# v11.net
KiCad netlist of a schematic drawn in EAGLE
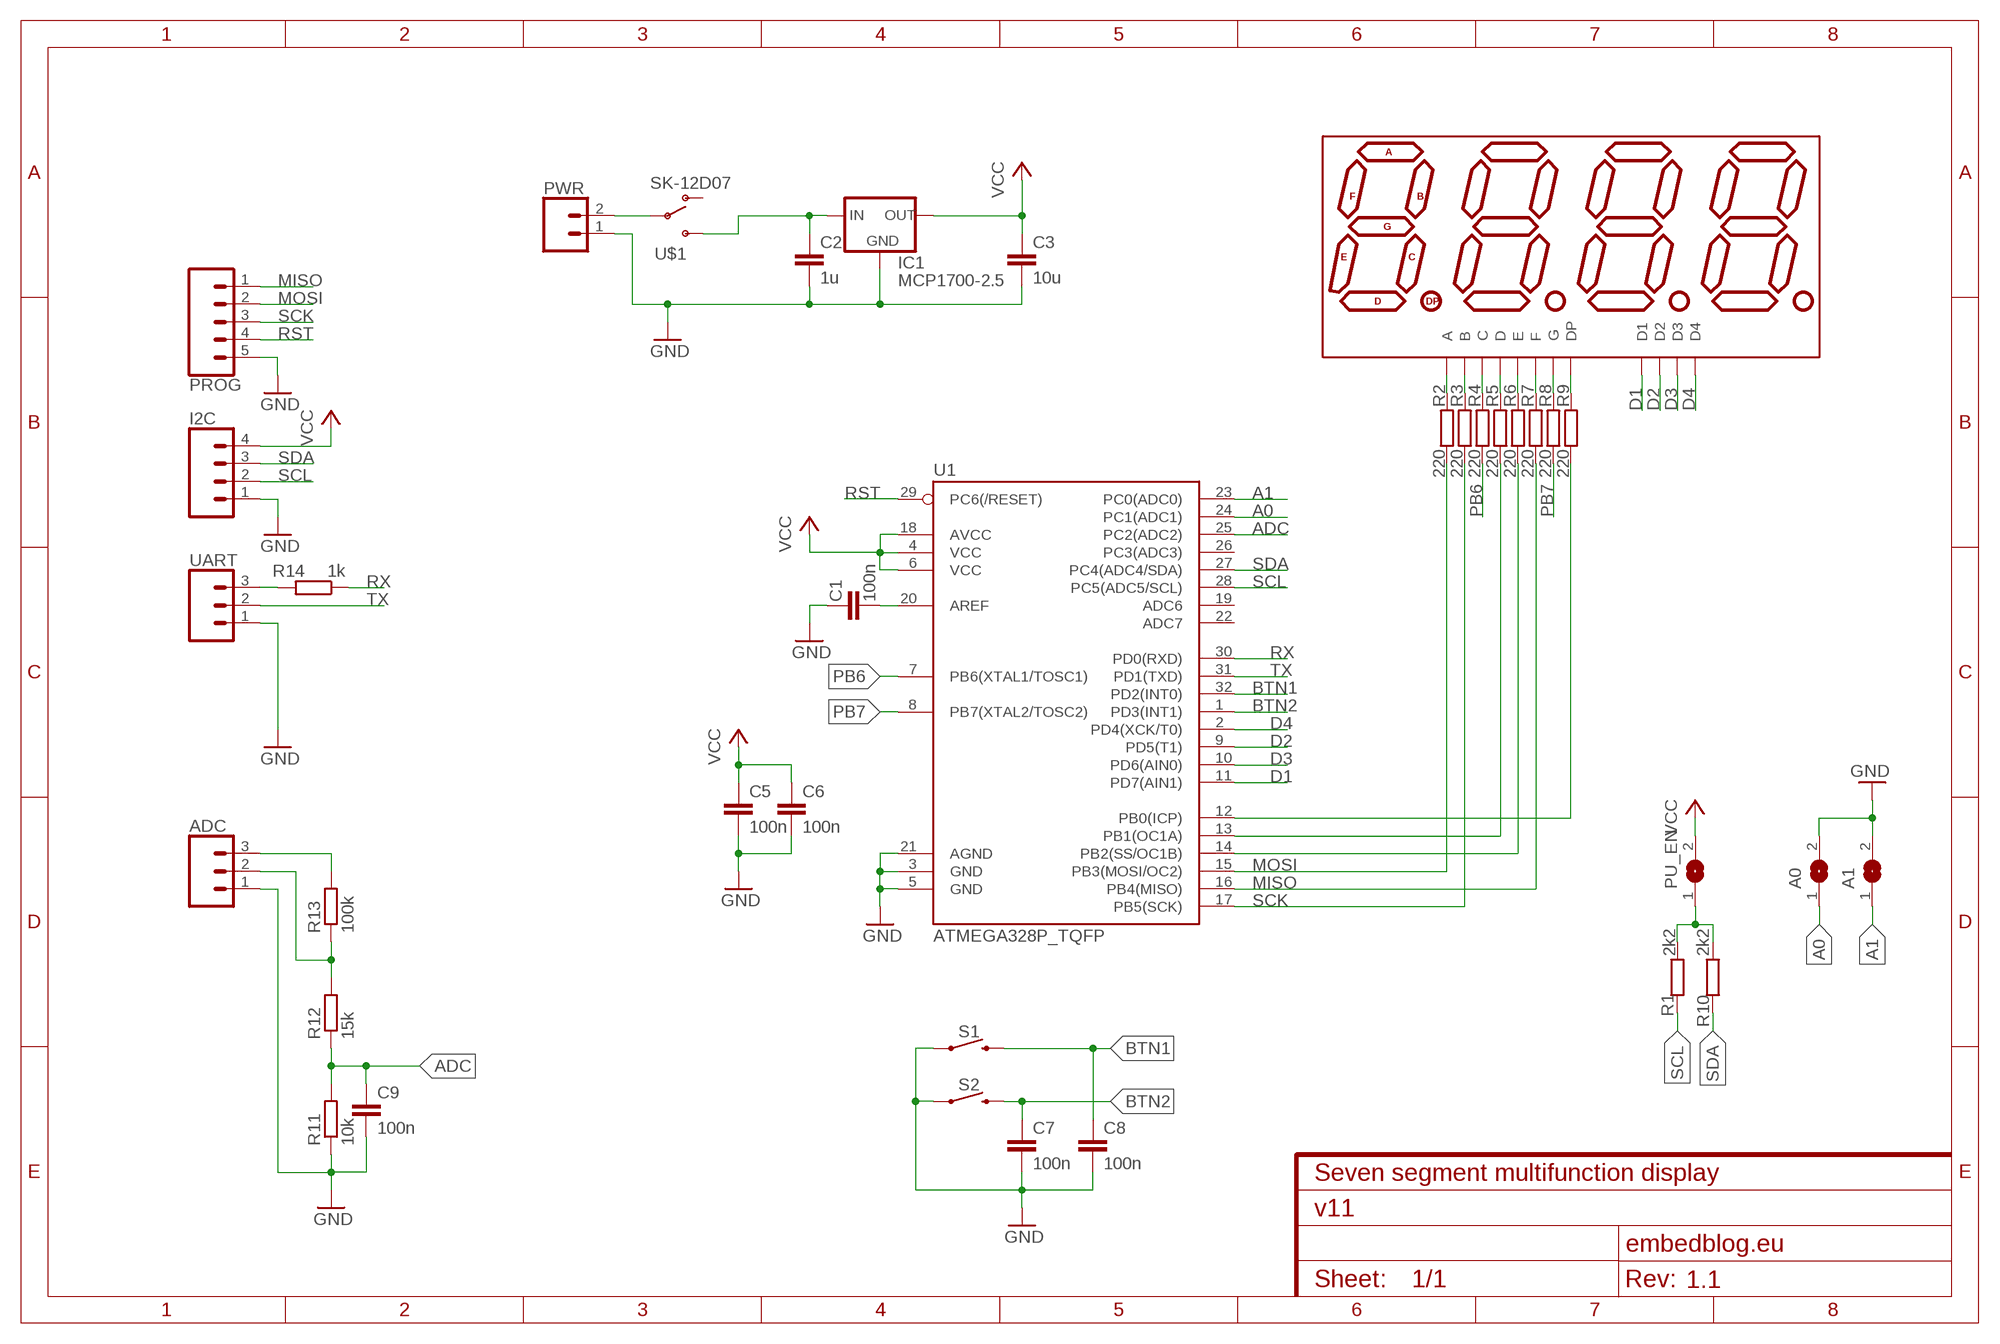
[diagram p0: schematic, sheet 1]

(export (version "E")
  (design (tool "Eeschema 10.0.6"))
  (components
    (comp (ref "A0") (value "SJ") (footprint "eagle-import:SJ") (libsource (lib "eagle-import") (part "SJ")))
    (comp (ref "A1") (value "SJ") (footprint "eagle-import:SJ") (libsource (lib "eagle-import") (part "SJ")))
    (comp (ref "ADC")
      (value "455-1750-1-ND")
      (footprint "eagle-import:1X03")
      (libsource (lib "eagle-import") (part "CONN_03"))
    )
    (comp (ref "C1")
      (value "100n")
      (footprint "eagle-import:C1206")
      (libsource (lib "eagle-import") (part "C-EUC1206"))
    )
    (comp (ref "C2")
      (value "1u")
      (footprint "eagle-import:C1206")
      (libsource (lib "eagle-import") (part "C-EUC1206"))
    )
    (comp (ref "C3")
      (value "10u")
      (footprint "eagle-import:C1206")
      (libsource (lib "eagle-import") (part "C-EUC1206"))
    )
    (comp (ref "C5")
      (value "100n")
      (footprint "eagle-import:C1206")
      (libsource (lib "eagle-import") (part "C-EUC1206"))
    )
    (comp (ref "C6")
      (value "100n")
      (footprint "eagle-import:C1206")
      (libsource (lib "eagle-import") (part "C-EUC1206"))
    )
    (comp (ref "C7")
      (value "100n")
      (footprint "eagle-import:C1206")
      (libsource (lib "eagle-import") (part "C-EUC1206"))
    )
    (comp (ref "C8")
      (value "100n")
      (footprint "eagle-import:C1206")
      (libsource (lib "eagle-import") (part "C-EUC1206"))
    )
    (comp (ref "C9")
      (value "100n")
      (footprint "eagle-import:C1206")
      (libsource (lib "eagle-import") (part "C-EUC1206"))
    )
    (comp (ref "D1")
      (value "7-SEG_0.56INCH")
      (footprint "eagle-import:7SEG_0.56INCH")
      (libsource (lib "eagle-import") (part "7-SEG_0.56INCH"))
    )
    (comp (ref "I2C")
      (value "CONN_04")
      (footprint "eagle-import:1X04")
      (libsource (lib "eagle-import") (part "CONN_04"))
    )
    (comp (ref "IC1")
      (value "MCP1700-2.5")
      (footprint "eagle-import:SOT23")
      (libsource (lib "eagle-import") (part "XC63FPM"))
    )
    (comp (ref "PROG")
      (value "CONN_05")
      (footprint "eagle-import:1X05")
      (libsource (lib "eagle-import") (part "CONN_05"))
    )
    (comp (ref "PU_EN")
      (value "SJ")
      (footprint "eagle-import:SJ")
      (libsource (lib "eagle-import") (part "SJ"))
    )
    (comp (ref "PWR")
      (value "CONN_02")
      (footprint "eagle-import:1X02")
      (libsource (lib "eagle-import") (part "CONN_02"))
    )
    (comp (ref "R1")
      (value "2k2")
      (footprint "eagle-import:R1206")
      (libsource (lib "eagle-import") (part "R-EU_R1206"))
    )
    (comp (ref "R2")
      (value "220")
      (footprint "eagle-import:R1206")
      (libsource (lib "eagle-import") (part "R-EU_R1206"))
    )
    (comp (ref "R3")
      (value "220")
      (footprint "eagle-import:R1206")
      (libsource (lib "eagle-import") (part "R-EU_R1206"))
    )
    (comp (ref "R4")
      (value "220")
      (footprint "eagle-import:R1206")
      (libsource (lib "eagle-import") (part "R-EU_R1206"))
    )
    (comp (ref "R5")
      (value "220")
      (footprint "eagle-import:R1206")
      (libsource (lib "eagle-import") (part "R-EU_R1206"))
    )
    (comp (ref "R6")
      (value "220")
      (footprint "eagle-import:R1206")
      (libsource (lib "eagle-import") (part "R-EU_R1206"))
    )
    (comp (ref "R7")
      (value "220")
      (footprint "eagle-import:R1206")
      (libsource (lib "eagle-import") (part "R-EU_R1206"))
    )
    (comp (ref "R8")
      (value "220")
      (footprint "eagle-import:R1206")
      (libsource (lib "eagle-import") (part "R-EU_R1206"))
    )
    (comp (ref "R9")
      (value "220")
      (footprint "eagle-import:R1206")
      (libsource (lib "eagle-import") (part "R-EU_R1206"))
    )
    (comp (ref "R10")
      (value "2k2")
      (footprint "eagle-import:R1206")
      (libsource (lib "eagle-import") (part "R-EU_R1206"))
    )
    (comp (ref "R11")
      (value "10k")
      (footprint "eagle-import:R1206")
      (libsource (lib "eagle-import") (part "R-EU_R1206"))
    )
    (comp (ref "R12")
      (value "15k")
      (footprint "eagle-import:R1206")
      (libsource (lib "eagle-import") (part "R-EU_R1206"))
    )
    (comp (ref "R13")
      (value "100k")
      (footprint "eagle-import:R1206")
      (libsource (lib "eagle-import") (part "R-EU_R1206"))
    )
    (comp (ref "R14")
      (value "1k")
      (footprint "eagle-import:R1206")
      (libsource (lib "eagle-import") (part "R-EU_R1206"))
    )
    (comp (ref "S1")
      (value "MOMENTARY-SWITCH-SPST-PTH-6.0MM")
      (footprint "eagle-import:TACTILE_SWITCH_PTH_6.0MM")
      (libsource (lib "eagle-import") (part "MOMENTARY-SWITCH-SPST-PTH-6.0MM"))
    )
    (comp (ref "S2")
      (value "MOMENTARY-SWITCH-SPST-PTH-6.0MM")
      (footprint "eagle-import:TACTILE_SWITCH_PTH_6.0MM")
      (libsource (lib "eagle-import") (part "MOMENTARY-SWITCH-SPST-PTH-6.0MM"))
    )
    (comp (ref "U$1")
      (value "SK-12D07")
      (footprint "eagle-import:SK12SWITCH")
      (libsource (lib "eagle-import") (part "SK-12D07"))
    )
    (comp (ref "U1")
      (value "ATMEGA328P_TQFP")
      (footprint "eagle-import:TQFP32-08")
      (libsource (lib "eagle-import") (part "ATMEGA328P_TQFP"))
    )
    (comp (ref "UART")
      (value "455-1750-1-ND")
      (footprint "eagle-import:1X03")
      (libsource (lib "eagle-import") (part "CONN_03"))
    )
  )
  (nets
    (net (code "1") (name "/D1") (class "Default")
      (node (ref "D1") (pin "D1") (pinfunction "D1_D1") (pintype "bidirectional"))
      (node (ref "U1") (pin "11") (pinfunction "PD7(AIN1)_11") (pintype "bidirectional"))
    )
    (net (code "2") (name "/D2") (class "Default")
      (node (ref "D1") (pin "D2") (pinfunction "D2_D2") (pintype "bidirectional"))
      (node (ref "U1") (pin "9") (pinfunction "PD5(T1)_9") (pintype "bidirectional"))
    )
    (net (code "3") (name "/D3") (class "Default")
      (node (ref "D1") (pin "D3") (pinfunction "D3_D3") (pintype "bidirectional"))
      (node (ref "U1") (pin "10") (pinfunction "PD6(AIN0)_10") (pintype "bidirectional"))
    )
    (net (code "4") (name "/D4") (class "Default")
      (node (ref "D1") (pin "D4") (pinfunction "D4_D4") (pintype "bidirectional"))
      (node (ref "U1") (pin "2") (pinfunction "PD4(XCK/T0)_2") (pintype "bidirectional"))
    )
    (net (code "5") (name "/MISO") (class "Default")
      (node (ref "PROG") (pin "1") (pinfunction "1_1") (pintype "passive"))
      (node (ref "R7") (pin "1") (pinfunction "1_1") (pintype "passive"))
      (node (ref "U1") (pin "16") (pinfunction "PB4(MISO)_16") (pintype "bidirectional"))
    )
    (net (code "6") (name "/MOSI") (class "Default")
      (node (ref "PROG") (pin "2") (pinfunction "2_2") (pintype "passive"))
      (node (ref "R2") (pin "1") (pinfunction "1_1") (pintype "passive"))
      (node (ref "U1") (pin "15") (pinfunction "PB3(MOSI/OC2)_15") (pintype "bidirectional"))
    )
    (net (code "7") (name "/RST") (class "Default")
      (node (ref "PROG") (pin "4") (pinfunction "4_4") (pintype "passive"))
      (node (ref "U1") (pin "29") (pinfunction "PC6(/RESET)_29") (pintype "bidirectional"))
    )
    (net (code "8") (name "/RX") (class "Default")
      (node (ref "R14") (pin "1") (pinfunction "1_1") (pintype "passive"))
      (node (ref "U1") (pin "30") (pinfunction "PD0(RXD)_30") (pintype "bidirectional"))
    )
    (net (code "9") (name "/SCK") (class "Default")
      (node (ref "PROG") (pin "3") (pinfunction "3_3") (pintype "passive"))
      (node (ref "R3") (pin "1") (pinfunction "1_1") (pintype "passive"))
      (node (ref "U1") (pin "17") (pinfunction "PB5(SCK)_17") (pintype "bidirectional"))
    )
    (net (code "10") (name "/TX") (class "Default")
      (node (ref "U1") (pin "31") (pinfunction "PD1(TXD)_31") (pintype "bidirectional"))
      (node (ref "UART") (pin "2") (pinfunction "2_2") (pintype "passive"))
    )
    (net (code "11") (name "A0") (class "Default")
      (node (ref "A0") (pin "1") (pinfunction "1_1") (pintype "passive"))
      (node (ref "U1") (pin "24") (pinfunction "PC1(ADC1)_24") (pintype "bidirectional"))
    )
    (net (code "12") (name "A1") (class "Default")
      (node (ref "A1") (pin "1") (pinfunction "1_1") (pintype "passive"))
      (node (ref "U1") (pin "23") (pinfunction "PC0(ADC0)_23") (pintype "bidirectional"))
    )
    (net (code "13") (name "ADC") (class "Default")
      (node (ref "C9") (pin "1") (pinfunction "1_1") (pintype "passive"))
      (node (ref "R11") (pin "2") (pinfunction "2_2") (pintype "passive"))
      (node (ref "R12") (pin "1") (pinfunction "1_1") (pintype "passive"))
      (node (ref "U1") (pin "25") (pinfunction "PC2(ADC2)_25") (pintype "bidirectional"))
    )
    (net (code "14") (name "BTN1") (class "Default")
      (node (ref "C8") (pin "1") (pinfunction "1_1") (pintype "passive"))
      (node (ref "S1") (pin "3") (pinfunction "2_3") (pintype "passive"))
      (node (ref "U1") (pin "32") (pinfunction "PD2(INT0)_32") (pintype "bidirectional"))
    )
    (net (code "15") (name "BTN2") (class "Default")
      (node (ref "C7") (pin "1") (pinfunction "1_1") (pintype "passive"))
      (node (ref "S2") (pin "3") (pinfunction "2_3") (pintype "passive"))
      (node (ref "U1") (pin "1") (pinfunction "PD3(INT1)_1") (pintype "bidirectional"))
    )
    (net (code "16") (name "GND") (class "Default")
      (node (ref "A0") (pin "2") (pinfunction "2_2") (pintype "passive"))
      (node (ref "A1") (pin "2") (pinfunction "2_2") (pintype "passive"))
      (node (ref "ADC") (pin "1") (pinfunction "1_1") (pintype "passive"))
      (node (ref "C1") (pin "1") (pinfunction "1_1") (pintype "passive"))
      (node (ref "C2") (pin "2") (pinfunction "2_2") (pintype "passive"))
      (node (ref "C3") (pin "2") (pinfunction "2_2") (pintype "passive"))
      (node (ref "C5") (pin "2") (pinfunction "2_2") (pintype "passive"))
      (node (ref "C6") (pin "2") (pinfunction "2_2") (pintype "passive"))
      (node (ref "C7") (pin "2") (pinfunction "2_2") (pintype "passive"))
      (node (ref "C8") (pin "2") (pinfunction "2_2") (pintype "passive"))
      (node (ref "C9") (pin "2") (pinfunction "2_2") (pintype "passive"))
      (node (ref "I2C") (pin "1") (pinfunction "1_1") (pintype "passive"))
      (node (ref "IC1") (pin "1") (pinfunction "GND_1") (pintype "input"))
      (node (ref "PROG") (pin "5") (pinfunction "5_5") (pintype "passive"))
      (node (ref "PWR") (pin "1") (pinfunction "1_1") (pintype "passive"))
      (node (ref "R11") (pin "1") (pinfunction "1_1") (pintype "passive"))
      (node (ref "S1") (pin "1") (pinfunction "1_1") (pintype "passive"))
      (node (ref "S2") (pin "1") (pinfunction "1_1") (pintype "passive"))
      (node (ref "U1") (pin "21") (pinfunction "AGND_21") (pintype "bidirectional"))
      (node (ref "U1") (pin "3") (pinfunction "GND_3") (pintype "bidirectional"))
      (node (ref "U1") (pin "5") (pinfunction "GND_5") (pintype "bidirectional"))
      (node (ref "UART") (pin "1") (pinfunction "1_1") (pintype "passive"))
    )
    (net (code "17") (name "Net-(ADC-Pad2)") (class "Default")
      (node (ref "ADC") (pin "2") (pinfunction "2_2") (pintype "passive"))
      (node (ref "R12") (pin "2") (pinfunction "2_2") (pintype "passive"))
      (node (ref "R13") (pin "1") (pinfunction "1_1") (pintype "passive"))
    )
    (net (code "18") (name "Net-(ADC-Pad3)") (class "Default")
      (node (ref "ADC") (pin "3") (pinfunction "3_3") (pintype "passive"))
      (node (ref "R13") (pin "2") (pinfunction "2_2") (pintype "passive"))
    )
    (net (code "19") (name "Net-(D1-PadA)") (class "Default")
      (node (ref "D1") (pin "A") (pinfunction "A_A") (pintype "bidirectional"))
      (node (ref "R2") (pin "2") (pinfunction "2_2") (pintype "passive"))
    )
    (net (code "20") (name "Net-(D1-PadB)") (class "Default")
      (node (ref "D1") (pin "B") (pinfunction "B_B") (pintype "bidirectional"))
      (node (ref "R3") (pin "2") (pinfunction "2_2") (pintype "passive"))
    )
    (net (code "21") (name "Net-(D1-PadC)") (class "Default")
      (node (ref "D1") (pin "C") (pinfunction "C_C") (pintype "bidirectional"))
      (node (ref "R4") (pin "2") (pinfunction "2_2") (pintype "passive"))
    )
    (net (code "22") (name "Net-(D1-PadD)") (class "Default")
      (node (ref "D1") (pin "D") (pinfunction "D_D") (pintype "bidirectional"))
      (node (ref "R5") (pin "2") (pinfunction "2_2") (pintype "passive"))
    )
    (net (code "23") (name "Net-(D1-PadDP)") (class "Default")
      (node (ref "D1") (pin "DP") (pinfunction "DP_DP") (pintype "bidirectional"))
      (node (ref "R9") (pin "2") (pinfunction "2_2") (pintype "passive"))
    )
    (net (code "24") (name "Net-(D1-PadE)") (class "Default")
      (node (ref "D1") (pin "E") (pinfunction "E_E") (pintype "bidirectional"))
      (node (ref "R6") (pin "2") (pinfunction "2_2") (pintype "passive"))
    )
    (net (code "25") (name "Net-(D1-PadF)") (class "Default")
      (node (ref "D1") (pin "F") (pinfunction "F_F") (pintype "bidirectional"))
      (node (ref "R7") (pin "2") (pinfunction "2_2") (pintype "passive"))
    )
    (net (code "26") (name "Net-(D1-PadG)") (class "Default")
      (node (ref "D1") (pin "G") (pinfunction "G_G") (pintype "bidirectional"))
      (node (ref "R8") (pin "2") (pinfunction "2_2") (pintype "passive"))
    )
    (net (code "27") (name "Net-(IC1-IN)") (class "Default")
      (node (ref "C2") (pin "1") (pinfunction "1_1") (pintype "passive"))
      (node (ref "IC1") (pin "3") (pinfunction "IN_3") (pintype "input"))
      (node (ref "U$1") (pin "IN") (pinfunction "S_IN") (pintype "passive"))
    )
    (net (code "28") (name "Net-(PU_EN-Pad1)") (class "Default")
      (node (ref "PU_EN") (pin "1") (pinfunction "1_1") (pintype "passive"))
      (node (ref "R1") (pin "2") (pinfunction "2_2") (pintype "passive"))
      (node (ref "R10") (pin "2") (pinfunction "2_2") (pintype "passive"))
    )
    (net (code "29") (name "Net-(R14-Pad2)") (class "Default")
      (node (ref "R14") (pin "2") (pinfunction "2_2") (pintype "passive"))
      (node (ref "UART") (pin "3") (pinfunction "3_3") (pintype "passive"))
    )
    (net (code "30") (name "Net-(U$1-P)") (class "Default")
      (node (ref "PWR") (pin "2") (pinfunction "2_2") (pintype "passive"))
      (node (ref "U$1") (pin "P2") (pinfunction "P_P2") (pintype "passive"))
    )
    (net (code "31") (name "Net-(U1-AREF)") (class "Default")
      (node (ref "C1") (pin "2") (pinfunction "2_2") (pintype "passive"))
      (node (ref "U1") (pin "20") (pinfunction "AREF_20") (pintype "bidirectional"))
    )
    (net (code "32") (name "Net-(U1-PB0(ICP))") (class "Default")
      (node (ref "R9") (pin "1") (pinfunction "1_1") (pintype "passive"))
      (node (ref "U1") (pin "12") (pinfunction "PB0(ICP)_12") (pintype "bidirectional"))
    )
    (net (code "33") (name "Net-(U1-PB1(OC1A))") (class "Default")
      (node (ref "R5") (pin "1") (pinfunction "1_1") (pintype "passive"))
      (node (ref "U1") (pin "13") (pinfunction "PB1(OC1A)_13") (pintype "bidirectional"))
    )
    (net (code "34") (name "Net-(U1-PB2(SS{slash}OC1B))") (class "Default")
      (node (ref "R6") (pin "1") (pinfunction "1_1") (pintype "passive"))
      (node (ref "U1") (pin "14") (pinfunction "PB2(SS/OC1B)_14") (pintype "bidirectional"))
    )
    (net (code "35") (name "PB6") (class "Default")
      (node (ref "R4") (pin "1") (pinfunction "1_1") (pintype "passive"))
      (node (ref "U1") (pin "7") (pinfunction "PB6(XTAL1/TOSC1)_7") (pintype "bidirectional"))
    )
    (net (code "36") (name "PB7") (class "Default")
      (node (ref "R8") (pin "1") (pinfunction "1_1") (pintype "passive"))
      (node (ref "U1") (pin "8") (pinfunction "PB7(XTAL2/TOSC2)_8") (pintype "bidirectional"))
    )
    (net (code "37") (name "SCL") (class "Default")
      (node (ref "I2C") (pin "2") (pinfunction "2_2") (pintype "passive"))
      (node (ref "R1") (pin "1") (pinfunction "1_1") (pintype "passive"))
      (node (ref "U1") (pin "28") (pinfunction "PC5(ADC5/SCL)_28") (pintype "bidirectional"))
    )
    (net (code "38") (name "SDA") (class "Default")
      (node (ref "I2C") (pin "3") (pinfunction "3_3") (pintype "passive"))
      (node (ref "R10") (pin "1") (pinfunction "1_1") (pintype "passive"))
      (node (ref "U1") (pin "27") (pinfunction "PC4(ADC4/SDA)_27") (pintype "bidirectional"))
    )
    (net (code "39") (name "VCC") (class "Default")
      (node (ref "C3") (pin "1") (pinfunction "1_1") (pintype "passive"))
      (node (ref "C5") (pin "1") (pinfunction "1_1") (pintype "passive"))
      (node (ref "C6") (pin "1") (pinfunction "1_1") (pintype "passive"))
      (node (ref "I2C") (pin "4") (pinfunction "4_4") (pintype "passive"))
      (node (ref "IC1") (pin "2") (pinfunction "OUT_2") (pintype "passive"))
      (node (ref "PU_EN") (pin "2") (pinfunction "2_2") (pintype "passive"))
      (node (ref "U1") (pin "18") (pinfunction "AVCC_18") (pintype "bidirectional"))
      (node (ref "U1") (pin "4") (pinfunction "VCC_4") (pintype "bidirectional"))
      (node (ref "U1") (pin "6") (pinfunction "VCC_6") (pintype "bidirectional"))
    )
    (net (code "40") (name "unconnected-(U$1-O-PadP1)") (class "Default")
      (node (ref "U$1") (pin "P1") (pinfunction "O_P1") (pintype "passive"))
    )
    (net (code "41") (name "unconnected-(U1-ADC6-Pad19)") (class "Default")
      (node (ref "U1") (pin "19") (pinfunction "ADC6_19") (pintype "bidirectional"))
    )
    (net (code "42") (name "unconnected-(U1-ADC7-Pad22)") (class "Default")
      (node (ref "U1") (pin "22") (pinfunction "ADC7_22") (pintype "bidirectional"))
    )
    (net (code "43") (name "unconnected-(U1-PC3(ADC3)-Pad26)") (class "Default")
      (node (ref "U1") (pin "26") (pinfunction "PC3(ADC3)_26") (pintype "bidirectional"))
    )
  )
)
